# BATTERY_PACK.net
KiCad netlist of a schematic drawn in Altium Designer
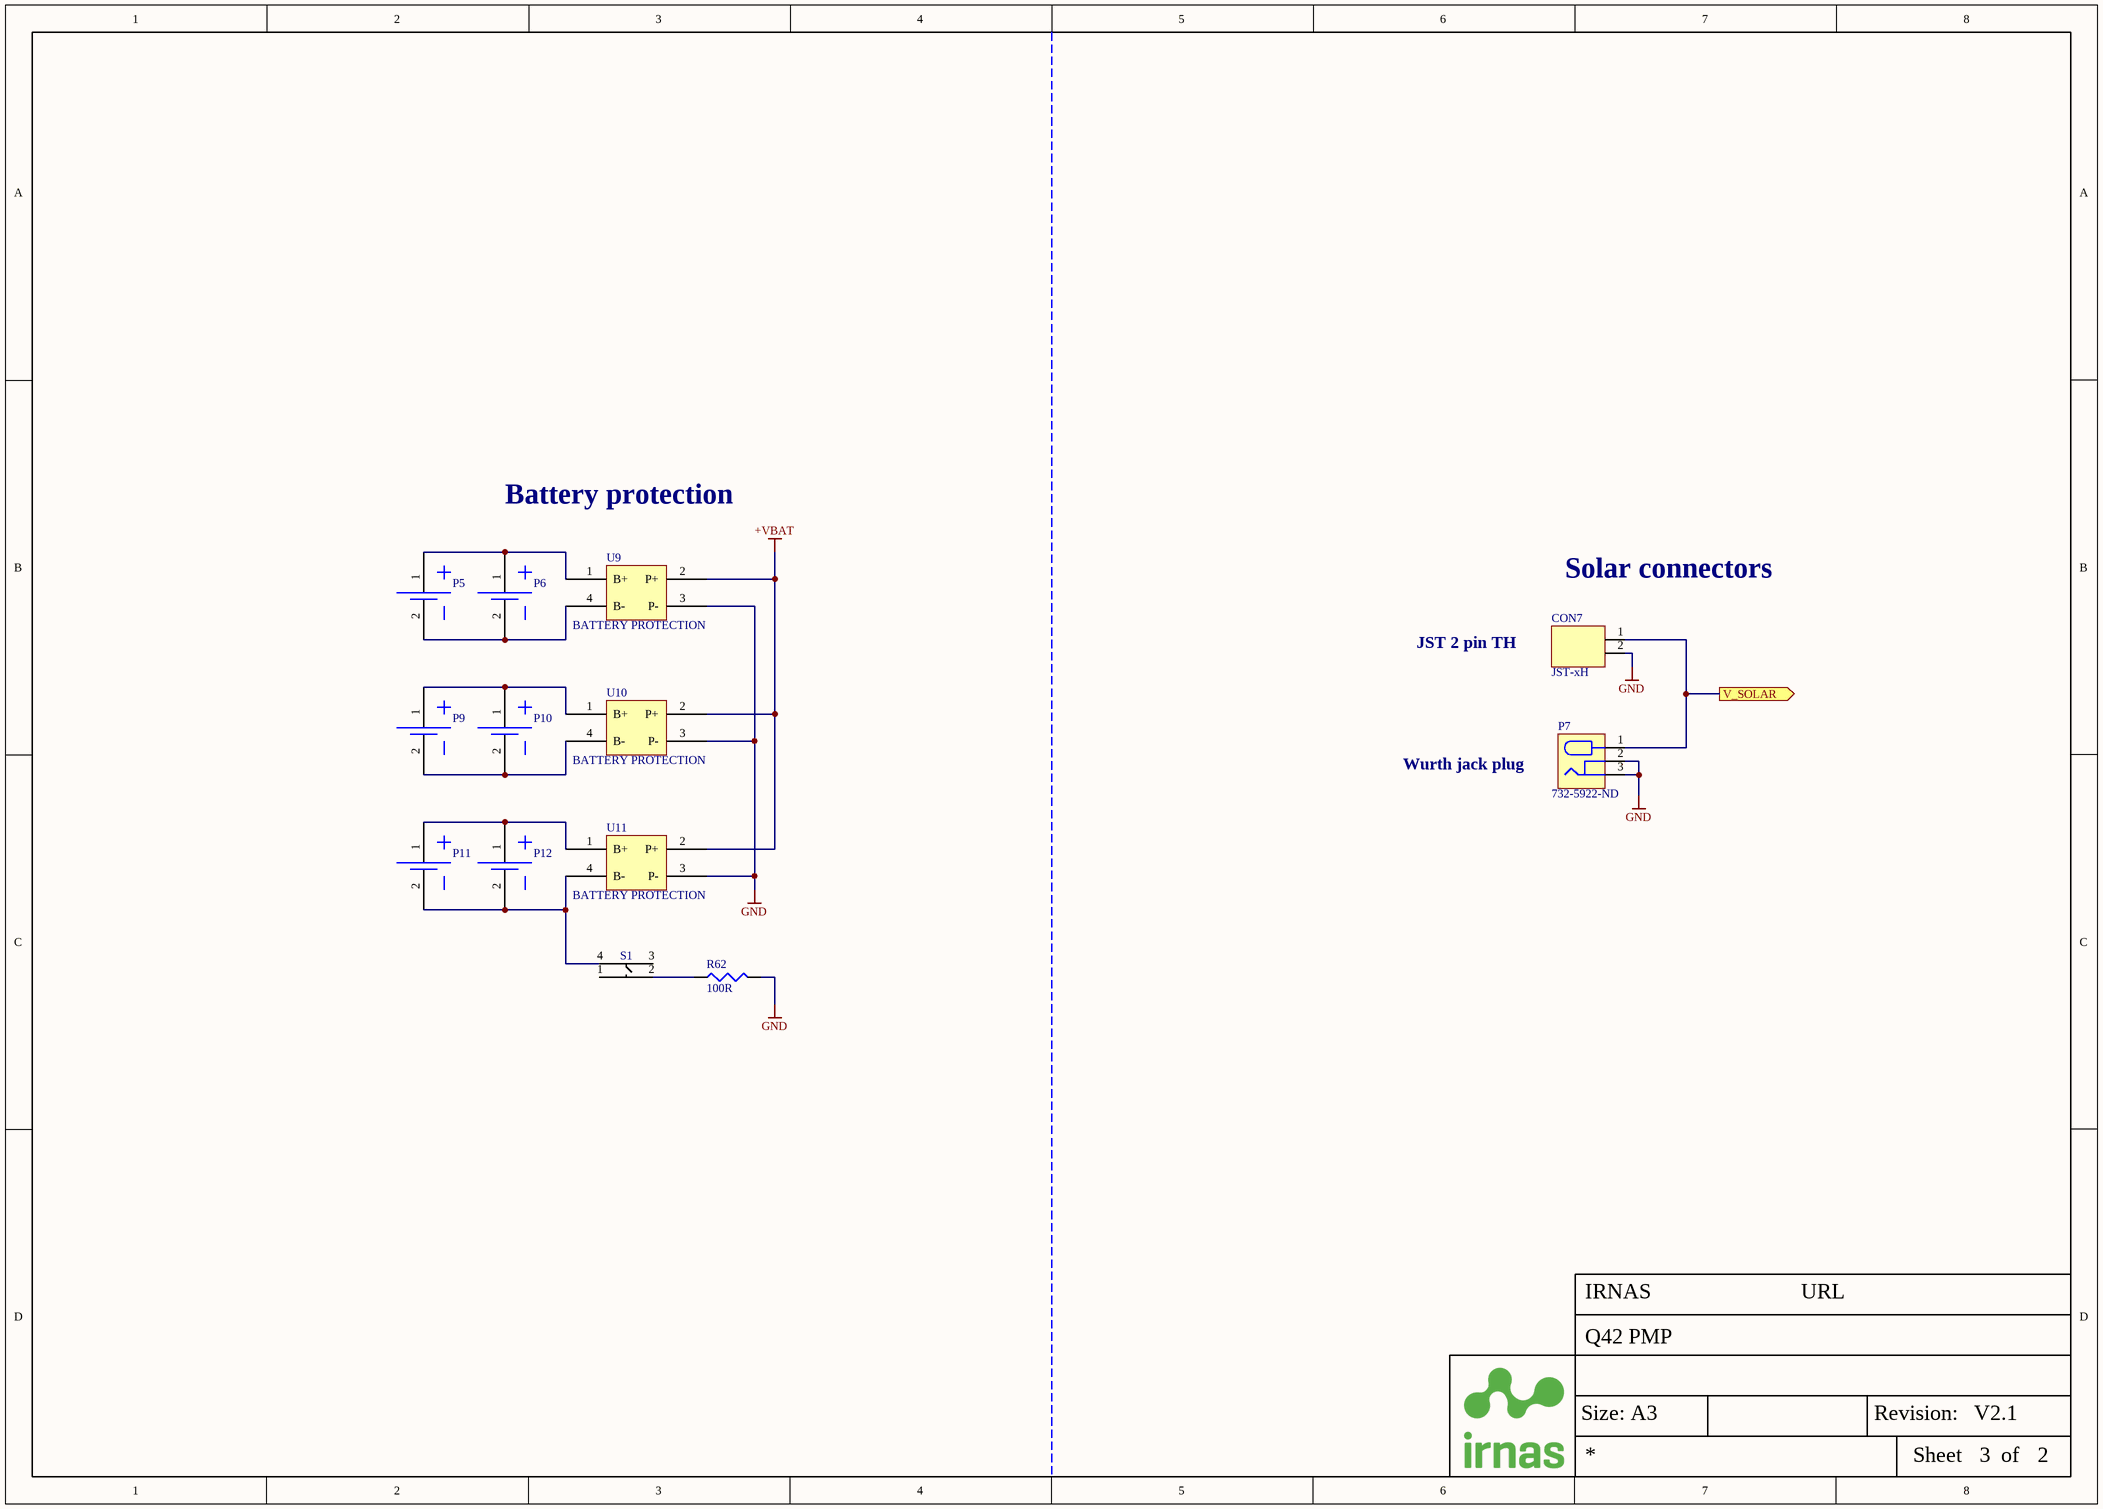
[diagram p0: BATTERY PACK.SchDoc]

(export (version "E")
  (design (tool "Eeschema 10.0.6"))
  (components
    (comp (ref "CON7")
      (value "JST-xH")
      (footprint "JST_2PIN_TH")
      (description "Wire-To-Board Connector, Vertical, 2.5 mm, 2 Contacts, Header, XH Series, Through Hole, 1 Rows")
      (libsource (lib "Connectors") (part "B2B-XH-A (LF)(SN)"))
    )
    (comp (ref "P5")
      (value "BAT - 18650")
      (footprint "BATTERY HOLDER 18650")
      (description "BATERRY HOLDER 18650")
      (libsource (lib "Mechanical") (part "BAT - 18650"))
    )
    (comp (ref "P6")
      (value "BAT - 18650")
      (footprint "BATTERY HOLDER 18650")
      (description "BATERRY HOLDER 18650")
      (libsource (lib "Mechanical") (part "BAT - 18650"))
    )
    (comp (ref "P7")
      (value "732-5922-ND")
      (footprint "732-5922-ND")
      (description "Power Barrel Connector Jack 1.05mm ID (0.041\"), 3.50mm OD (0.138\") Through Hole, Right Angle")
      (libsource (lib "Connectors") (part "CONN PWR JACK 1.05X3.5MM"))
    )
    (comp (ref "P9")
      (value "BAT - 18650")
      (footprint "BATTERY HOLDER 18650")
      (description "BATERRY HOLDER 18650")
      (libsource (lib "Mechanical") (part "BAT - 18650"))
    )
    (comp (ref "P10")
      (value "BAT - 18650")
      (footprint "BATTERY HOLDER 18650")
      (description "BATERRY HOLDER 18650")
      (libsource (lib "Mechanical") (part "BAT - 18650"))
    )
    (comp (ref "P11")
      (value "BAT - 18650")
      (footprint "BATTERY HOLDER 18650")
      (description "BATERRY HOLDER 18650")
      (libsource (lib "Mechanical") (part "BAT - 18650"))
    )
    (comp (ref "P12")
      (value "BAT - 18650")
      (footprint "BATTERY HOLDER 18650")
      (description "BATERRY HOLDER 18650")
      (libsource (lib "Mechanical") (part "BAT - 18650"))
    )
    (comp (ref "R62")
      (value "100R")
      (footprint "RES0603")
      (description "MULTICOMP - MC0063W06031100R - RES, THICK FILM, 100R, 1%, 0.063W, 0603")
      (fields
        (field (name "MANUFACTURER") "MULTICOMP")
        (field (name "MANUFACTURER PART NUMBER") "MC0063W06031100R")
      )
      (libsource (lib "Passive") (part "R - 100R"))
    )
    (comp (ref "S1")
      (value "BTN - KMR221NGLFS")
      (footprint "SW")
      (description "SWITCH TACTILE SPST-NO 0.05A 32V")
      (fields (field (name "MANUFACTURER") "ITT C&K") (field (name "MANUFACTURER PART NUMBER") "KMR221NGLFS"))
      (libsource (lib "Mechanical") (part "BTN - KMR221NGLFS"))
    )
    (comp (ref "U9")
      (value "BATTERY PROTECTION")
      (footprint "BATTERY PROTECTION")
      (libsource (lib "Mechanical") (part "BATTERY PROTECTION"))
    )
    (comp (ref "U10")
      (value "BATTERY PROTECTION")
      (footprint "BATTERY PROTECTION")
      (libsource (lib "Mechanical") (part "BATTERY PROTECTION"))
    )
    (comp (ref "U11")
      (value "BATTERY PROTECTION")
      (footprint "BATTERY PROTECTION")
      (libsource (lib "Mechanical") (part "BATTERY PROTECTION"))
    )
  )
  (nets
    (net (code "1") (name "+VBAT") (class "Default")
      (node (ref "U10") (pin "2") (pinfunction "P+_2") (pintype "passive"))
      (node (ref "U11") (pin "2") (pinfunction "P+_2") (pintype "passive"))
      (node (ref "U9") (pin "2") (pinfunction "P+_2") (pintype "passive"))
    )
    (net (code "2") (name "/V_SOLAR") (class "Default")
      (node (ref "CON7") (pin "1") (pinfunction "1_1") (pintype "passive"))
      (node (ref "P7") (pin "1") (pinfunction "1_1") (pintype "passive"))
    )
    (net (code "3") (name "GND") (class "Default")
      (node (ref "CON7") (pin "2") (pinfunction "2_2") (pintype "passive"))
      (node (ref "P7") (pin "2") (pinfunction "2_2") (pintype "passive"))
      (node (ref "P7") (pin "3") (pinfunction "3_3") (pintype "passive"))
      (node (ref "R62") (pin "2") (pinfunction "2_2") (pintype "passive"))
      (node (ref "U10") (pin "3") (pinfunction "P-_3") (pintype "passive"))
      (node (ref "U11") (pin "3") (pinfunction "P-_3") (pintype "passive"))
      (node (ref "U9") (pin "3") (pinfunction "P-_3") (pintype "passive"))
    )
    (net (code "4") (name "Net-(R62-Pad1)") (class "Default")
      (node (ref "R62") (pin "1") (pinfunction "1_1") (pintype "passive"))
      (node (ref "S1") (pin "2") (pinfunction "2_2") (pintype "passive"))
    )
    (net (code "5") (name "Net-(U9-B+)") (class "Default")
      (node (ref "P5") (pin "1") (pintype "passive"))
      (node (ref "P6") (pin "1") (pintype "passive"))
      (node (ref "U9") (pin "1") (pinfunction "B+_1") (pintype "passive"))
    )
    (net (code "6") (name "Net-(U9-B-)") (class "Default")
      (node (ref "P5") (pin "2") (pintype "passive"))
      (node (ref "P6") (pin "2") (pintype "passive"))
      (node (ref "U9") (pin "4") (pinfunction "B-_4") (pintype "passive"))
    )
    (net (code "7") (name "Net-(U10-B+)") (class "Default")
      (node (ref "P10") (pin "1") (pintype "passive"))
      (node (ref "P9") (pin "1") (pintype "passive"))
      (node (ref "U10") (pin "1") (pinfunction "B+_1") (pintype "passive"))
    )
    (net (code "8") (name "Net-(U10-B-)") (class "Default")
      (node (ref "P10") (pin "2") (pintype "passive"))
      (node (ref "P9") (pin "2") (pintype "passive"))
      (node (ref "U10") (pin "4") (pinfunction "B-_4") (pintype "passive"))
    )
    (net (code "9") (name "Net-(U11-B+)") (class "Default")
      (node (ref "P11") (pin "1") (pintype "passive"))
      (node (ref "P12") (pin "1") (pintype "passive"))
      (node (ref "U11") (pin "1") (pinfunction "B+_1") (pintype "passive"))
    )
    (net (code "10") (name "Net-(U11-B-)") (class "Default")
      (node (ref "P11") (pin "2") (pintype "passive"))
      (node (ref "P12") (pin "2") (pintype "passive"))
      (node (ref "S1") (pin "4") (pinfunction "4_4") (pintype "passive"))
      (node (ref "U11") (pin "4") (pinfunction "B-_4") (pintype "passive"))
    )
    (net (code "11") (name "unconnected-(S1-Pad1)") (class "Default")
      (node (ref "S1") (pin "1") (pinfunction "1_1") (pintype "passive"))
    )
    (net (code "12") (name "unconnected-(S1-Pad3)") (class "Default")
      (node (ref "S1") (pin "3") (pinfunction "3_3") (pintype "passive"))
    )
  )
)
